# programmer_charter.net
KiCad netlist of a schematic drawn in Altium Designer
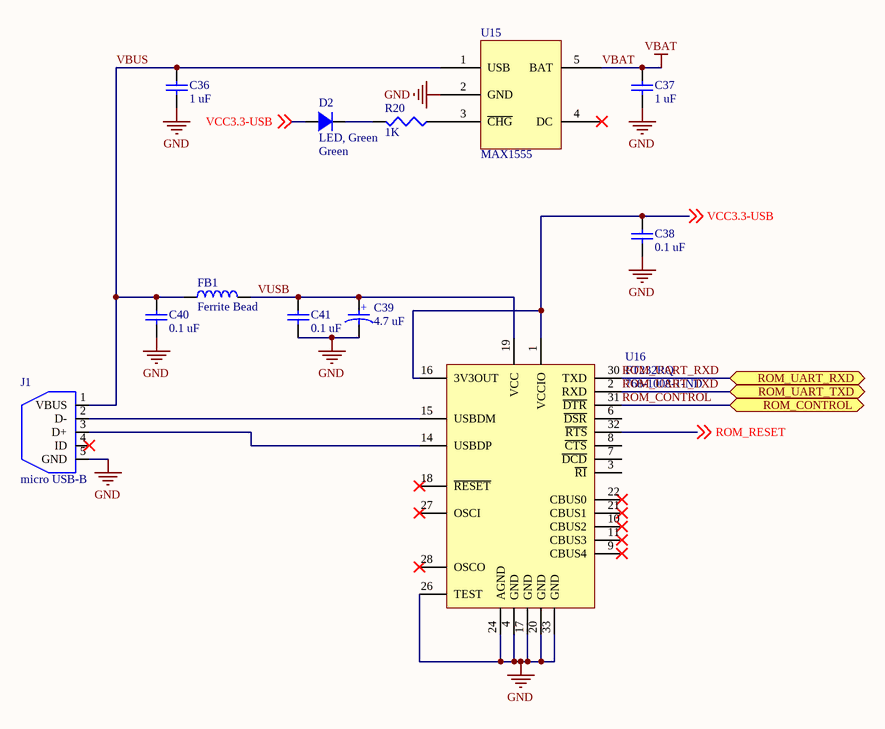
[diagram p0: programmer_charter.SchDoc]

(export (version "E")
  (design (tool "Eeschema 10.0.6"))
  (components
    (comp (ref "C36")
      (value "1 uF")
      (footprint "0402")
      (description "Ceramic capacitor, 1 uF, 0402 package")
      (fields (field (name "TOLERANCE") "10%") (field (name "Comment") "Ceramic capacitor"))
      (libsource (lib "rlc") (part "C_1u_0402_ceramic"))
    )
    (comp (ref "C37")
      (value "1 uF")
      (footprint "0402")
      (description "Ceramic capacitor, 1 uF, 0402 package")
      (fields (field (name "TOLERANCE") "10%") (field (name "Comment") "Ceramic capacitor"))
      (libsource (lib "rlc") (part "C_1u_0402_ceramic"))
    )
    (comp (ref "C38")
      (value "0.1 uF")
      (footprint "0402")
      (description "Ceramic capacitor, 0.1u, 0402 package")
      (fields (field (name "TOLERANCE") "10%") (field (name "Comment") "Ceramic capacitor"))
      (libsource (lib "rlc") (part "C_0.1u_0402_ceramic"))
    )
    (comp (ref "C39")
      (value "4.7 uF")
      (footprint "0603 - Polar Marking")
      (description "Tantalum capacitor, 4.7 uF, 0603 package")
      (fields (field (name "TOLERANCE") "20%") (field (name "Comment") "Tantalum capacitor"))
      (libsource (lib "rlc") (part "C_4.7u_0603_tantalum"))
    )
    (comp (ref "C40")
      (value "0.1 uF")
      (footprint "0402")
      (description "Ceramic capacitor, 0.1u, 0402 package")
      (fields (field (name "TOLERANCE") "10%") (field (name "Comment") "Ceramic capacitor"))
      (libsource (lib "rlc") (part "C_0.1u_0402_ceramic"))
    )
    (comp (ref "C41")
      (value "0.1 uF")
      (footprint "0402")
      (description "Ceramic capacitor, 0.1u, 0402 package")
      (fields (field (name "TOLERANCE") "10%") (field (name "Comment") "Ceramic capacitor"))
      (libsource (lib "rlc") (part "C_0.1u_0402_ceramic"))
    )
    (comp (ref "D2")
      (value "LED, Green")
      (footprint "0402 - DIODE")
      (description "LED, Green,  0402")
      (fields (field (name "COLOR") "Green"))
      (libsource (lib "rlc") (part "D_LED_GREEN_0402"))
    )
    (comp (ref "FB1")
      (value "Ferrite Bead")
      (footprint "0402")
      (description "Ferrite Bead, 150 mA, 0402 package")
      (libsource (lib "rlc") (part "FB_150mA_0402"))
    )
    (comp (ref "J1")
      (value "micro USB-B")
      (footprint "Micro USB-B")
      (description "CONN USB MICRO B RECPT SMT R/A")
      (libsource (lib "opo_general") (part "Micro USB"))
    )
    (comp (ref "R20")
      (value "1K")
      (footprint "0402")
      (description "Chip resistor, 1K, 0402 package")
      (fields (field (name "TOLERANCE") "1%") (field (name "POWER") "1/16 W"))
      (libsource (lib "rlc") (part "R_1K_0402"))
    )
    (comp (ref "U15")
      (value "MAX1555")
      (footprint "SOT23-5")
      (description "3 Dual-Input USB/AC Adapter 1-Cell Li+  Battery Chargers")
      (libsource (lib "opo_general") (part "MAX1555"))
    )
    (comp (ref "U16")
      (value "FT232RQ")
      (footprint "QFN-32")
      (description "FT232R USB UART")
      (fields (field (name "SUPPLIER PART NUMBER 1") "768-1008-1-ND"))
      (libsource (lib "opo_general") (part "IC_FT232RQ"))
    )
  )
  (nets
    (net (code "1") (name "/ROM_CONTROL") (class "Default")
      (node (ref "U16") (pin "31") (pinfunction "~{DTR}_31") (pintype "passive"))
    )
    (net (code "2") (name "/ROM_UART_RXD") (class "Default")
      (node (ref "U16") (pin "30") (pinfunction "TXD_30") (pintype "passive"))
    )
    (net (code "3") (name "/ROM_UART_TXD") (class "Default")
      (node (ref "U16") (pin "2") (pinfunction "RXD_2") (pintype "passive"))
    )
    (net (code "4") (name "/VBUS") (class "Default")
      (node (ref "C36") (pin "1") (pintype "passive"))
      (node (ref "C40") (pin "1") (pintype "passive"))
      (node (ref "FB1") (pin "2") (pintype "passive"))
      (node (ref "J1") (pin "1") (pinfunction "VBUS_1") (pintype "power_in"))
      (node (ref "U15") (pin "1") (pinfunction "USB_1") (pintype "passive"))
    )
    (net (code "5") (name "/VUSB") (class "Default")
      (node (ref "C39") (pin "1") (pintype "passive"))
      (node (ref "C41") (pin "1") (pintype "passive"))
      (node (ref "FB1") (pin "1") (pintype "passive"))
      (node (ref "U16") (pin "19") (pinfunction "VCC_19") (pintype "passive"))
    )
    (net (code "6") (name "GND") (class "Default")
      (node (ref "C36") (pin "2") (pintype "passive"))
      (node (ref "C37") (pin "2") (pintype "passive"))
      (node (ref "C38") (pin "2") (pintype "passive"))
      (node (ref "C39") (pin "2") (pintype "passive"))
      (node (ref "C40") (pin "2") (pintype "passive"))
      (node (ref "C41") (pin "2") (pintype "passive"))
      (node (ref "J1") (pin "5") (pinfunction "GND_5") (pintype "power_in"))
      (node (ref "U15") (pin "2") (pinfunction "GND_2") (pintype "passive"))
      (node (ref "U16") (pin "17") (pinfunction "GND_17") (pintype "passive"))
      (node (ref "U16") (pin "20") (pinfunction "GND_20") (pintype "passive"))
      (node (ref "U16") (pin "24") (pinfunction "AGND_24") (pintype "passive"))
      (node (ref "U16") (pin "26") (pinfunction "TEST_26") (pintype "passive"))
      (node (ref "U16") (pin "33") (pinfunction "GND_33") (pintype "passive"))
      (node (ref "U16") (pin "4") (pinfunction "GND_4") (pintype "passive"))
    )
    (net (code "7") (name "Net-(D2-Pad2)") (class "Default")
      (node (ref "D2") (pin "2") (pintype "passive"))
      (node (ref "R20") (pin "1") (pintype "passive"))
    )
    (net (code "8") (name "Net-(J1-D+)") (class "Default")
      (node (ref "J1") (pin "3") (pinfunction "D+_3") (pintype "power_in"))
      (node (ref "U16") (pin "14") (pinfunction "USBDP_14") (pintype "passive"))
    )
    (net (code "9") (name "Net-(J1-D-)") (class "Default")
      (node (ref "J1") (pin "2") (pinfunction "D-_2") (pintype "power_in"))
      (node (ref "U16") (pin "15") (pinfunction "USBDM_15") (pintype "passive"))
    )
    (net (code "10") (name "Net-(U15-~{CHG})") (class "Default")
      (node (ref "R20") (pin "2") (pintype "passive"))
      (node (ref "U15") (pin "3") (pinfunction "~{CHG}_3") (pintype "passive"))
    )
    (net (code "11") (name "ROM_RESET") (class "Default")
      (node (ref "U16") (pin "32") (pinfunction "~{RTS}_32") (pintype "passive"))
    )
    (net (code "12") (name "VBAT") (class "Default")
      (node (ref "C37") (pin "1") (pintype "passive"))
      (node (ref "U15") (pin "5") (pinfunction "BAT_5") (pintype "passive"))
    )
    (net (code "13") (name "VCC3.3-USB") (class "Default")
      (node (ref "C38") (pin "1") (pintype "passive"))
      (node (ref "D2") (pin "1") (pintype "passive"))
      (node (ref "U16") (pin "1") (pinfunction "VCCIO_1") (pintype "passive"))
      (node (ref "U16") (pin "16") (pinfunction "3V3OUT_16") (pintype "passive"))
    )
    (net (code "14") (name "unconnected-(J1-ID-Pad4)") (class "Default")
      (node (ref "J1") (pin "4") (pinfunction "ID_4") (pintype "power_in+no_connect"))
    )
    (net (code "15") (name "unconnected-(U15-DC-Pad4)") (class "Default")
      (node (ref "U15") (pin "4") (pinfunction "DC_4") (pintype "passive+no_connect"))
    )
    (net (code "16") (name "unconnected-(U16-CBUS0-Pad22)") (class "Default")
      (node (ref "U16") (pin "22") (pinfunction "CBUS0_22") (pintype "passive+no_connect"))
    )
    (net (code "17") (name "unconnected-(U16-CBUS1-Pad21)") (class "Default")
      (node (ref "U16") (pin "21") (pinfunction "CBUS1_21") (pintype "passive+no_connect"))
    )
    (net (code "18") (name "unconnected-(U16-CBUS2-Pad10)") (class "Default")
      (node (ref "U16") (pin "10") (pinfunction "CBUS2_10") (pintype "passive+no_connect"))
    )
    (net (code "19") (name "unconnected-(U16-CBUS3-Pad11)") (class "Default")
      (node (ref "U16") (pin "11") (pinfunction "CBUS3_11") (pintype "passive+no_connect"))
    )
    (net (code "20") (name "unconnected-(U16-CBUS4-Pad9)") (class "Default")
      (node (ref "U16") (pin "9") (pinfunction "CBUS4_9") (pintype "passive+no_connect"))
    )
    (net (code "21") (name "unconnected-(U16-OSCI-Pad27)") (class "Default")
      (node (ref "U16") (pin "27") (pinfunction "OSCI_27") (pintype "passive+no_connect"))
    )
    (net (code "22") (name "unconnected-(U16-OSCO-Pad28)") (class "Default")
      (node (ref "U16") (pin "28") (pinfunction "OSCO_28") (pintype "passive+no_connect"))
    )
    (net (code "23") (name "unconnected-(U16-~{CTS}-Pad8)") (class "Default")
      (node (ref "U16") (pin "8") (pinfunction "~{CTS}_8") (pintype "passive"))
    )
    (net (code "24") (name "unconnected-(U16-~{DCD}-Pad7)") (class "Default")
      (node (ref "U16") (pin "7") (pinfunction "~{DCD}_7") (pintype "passive"))
    )
    (net (code "25") (name "unconnected-(U16-~{DSR}-Pad6)") (class "Default")
      (node (ref "U16") (pin "6") (pinfunction "~{DSR}_6") (pintype "passive"))
    )
    (net (code "26") (name "unconnected-(U16-~{RESET}-Pad18)") (class "Default")
      (node (ref "U16") (pin "18") (pinfunction "~{RESET}_18") (pintype "passive+no_connect"))
    )
    (net (code "27") (name "unconnected-(U16-~{RI}-Pad3)") (class "Default")
      (node (ref "U16") (pin "3") (pinfunction "~{RI}_3") (pintype "passive"))
    )
  )
)
